# murdock_top_v4.net
KiCad netlist of a schematic drawn in EAGLE
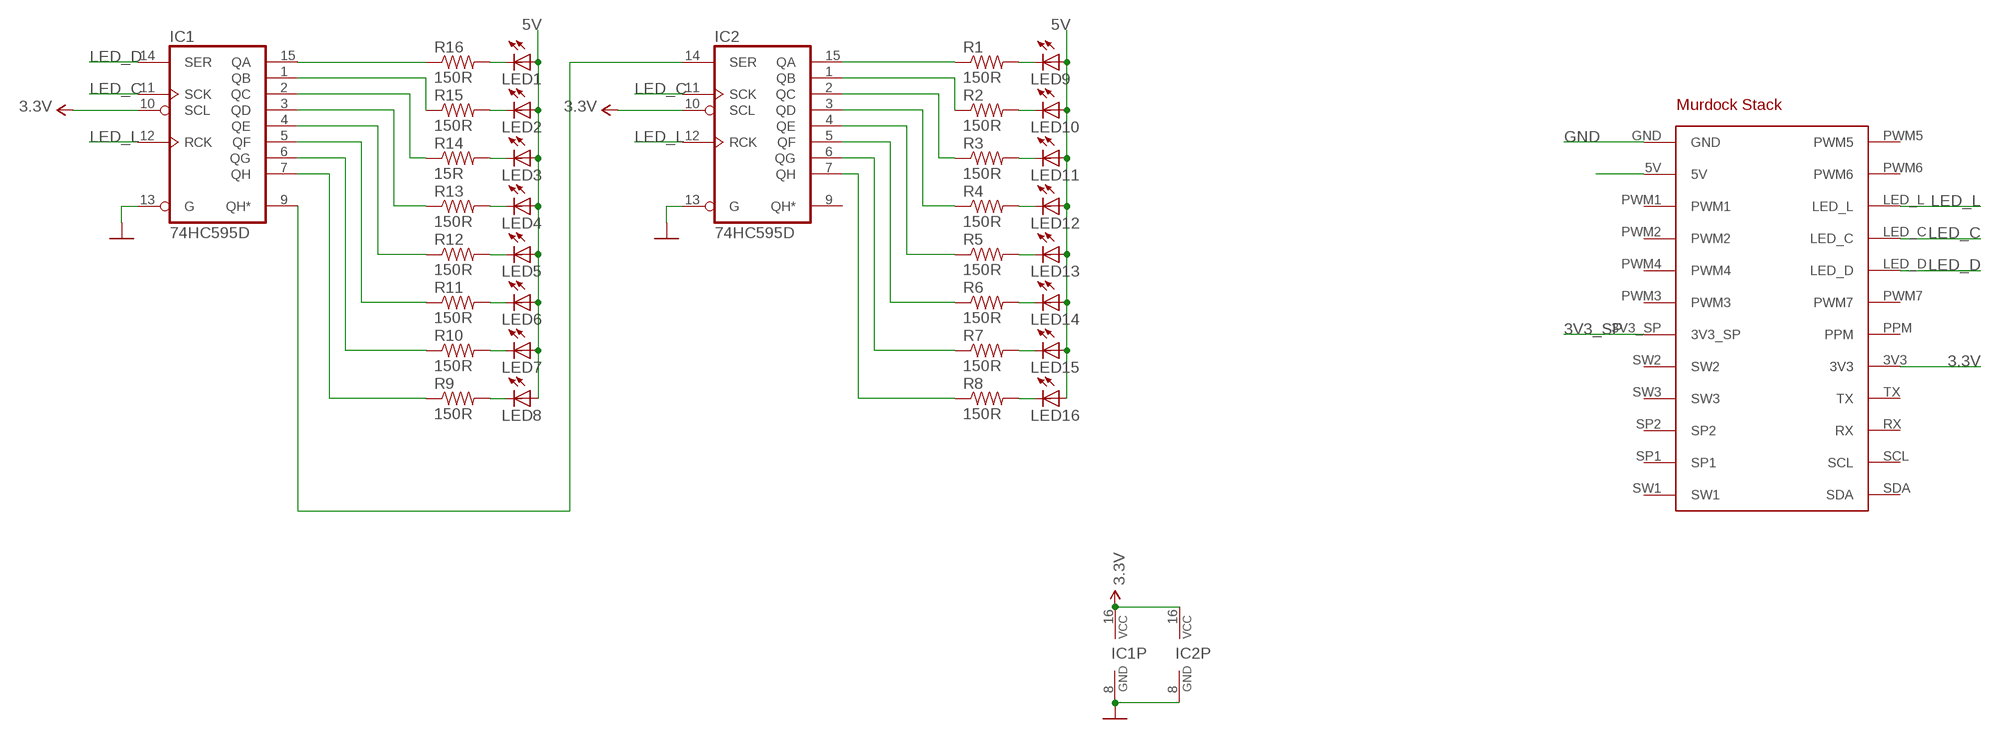
[diagram p0: schematic, sheet 1]

(export (version "E")
  (design (tool "Eeschema 10.0.6"))
  (components
    (comp (ref "IC1")
      (value "74HC595D")
      (footprint "eagle-import:SO16")
      (libsource (lib "eagle-import") (part "74595DHC"))
    )
    (comp (ref "IC2")
      (value "74HC595D")
      (footprint "eagle-import:SO16")
      (libsource (lib "eagle-import") (part "74595DHC"))
    )
    (comp (ref "LED1")
      (value "LGM47K")
      (footprint "eagle-import:LGM47K")
      (libsource (lib "eagle-import") (part "LGM47K"))
    )
    (comp (ref "LED2")
      (value "LGM47K")
      (footprint "eagle-import:LGM47K")
      (libsource (lib "eagle-import") (part "LGM47K"))
    )
    (comp (ref "LED3")
      (value "LGM47K")
      (footprint "eagle-import:LGM47K")
      (libsource (lib "eagle-import") (part "LGM47K"))
    )
    (comp (ref "LED4")
      (value "LGM47K")
      (footprint "eagle-import:LGM47K")
      (libsource (lib "eagle-import") (part "LGM47K"))
    )
    (comp (ref "LED5")
      (value "LGM47K")
      (footprint "eagle-import:LGM47K")
      (libsource (lib "eagle-import") (part "LGM47K"))
    )
    (comp (ref "LED6")
      (value "LGM47K")
      (footprint "eagle-import:LGM47K")
      (libsource (lib "eagle-import") (part "LGM47K"))
    )
    (comp (ref "LED7")
      (value "LGM47K")
      (footprint "eagle-import:LGM47K")
      (libsource (lib "eagle-import") (part "LGM47K"))
    )
    (comp (ref "LED8")
      (value "LGM47K")
      (footprint "eagle-import:LGM47K")
      (libsource (lib "eagle-import") (part "LGM47K"))
    )
    (comp (ref "LED9")
      (value "LGM47K")
      (footprint "eagle-import:LGM47K")
      (libsource (lib "eagle-import") (part "LGM47K"))
    )
    (comp (ref "LED10")
      (value "LGM47K")
      (footprint "eagle-import:LGM47K")
      (libsource (lib "eagle-import") (part "LGM47K"))
    )
    (comp (ref "LED11")
      (value "LGM47K")
      (footprint "eagle-import:LGM47K")
      (libsource (lib "eagle-import") (part "LGM47K"))
    )
    (comp (ref "LED12")
      (value "LGM47K")
      (footprint "eagle-import:LGM47K")
      (libsource (lib "eagle-import") (part "LGM47K"))
    )
    (comp (ref "LED13")
      (value "LGM47K")
      (footprint "eagle-import:LGM47K")
      (libsource (lib "eagle-import") (part "LGM47K"))
    )
    (comp (ref "LED14")
      (value "LGM47K")
      (footprint "eagle-import:LGM47K")
      (libsource (lib "eagle-import") (part "LGM47K"))
    )
    (comp (ref "LED15")
      (value "LGM47K")
      (footprint "eagle-import:LGM47K")
      (libsource (lib "eagle-import") (part "LGM47K"))
    )
    (comp (ref "LED16")
      (value "LGM47K")
      (footprint "eagle-import:LGM47K")
      (libsource (lib "eagle-import") (part "LGM47K"))
    )
    (comp (ref "R1")
      (value "150R")
      (footprint "eagle-import:0402-RES")
      (libsource (lib "eagle-import") (part "RESISTOR0402-RES"))
    )
    (comp (ref "R2")
      (value "150R")
      (footprint "eagle-import:0402-RES")
      (libsource (lib "eagle-import") (part "RESISTOR0402-RES"))
    )
    (comp (ref "R3")
      (value "150R")
      (footprint "eagle-import:0402-RES")
      (libsource (lib "eagle-import") (part "RESISTOR0402-RES"))
    )
    (comp (ref "R4")
      (value "150R")
      (footprint "eagle-import:0402-RES")
      (libsource (lib "eagle-import") (part "RESISTOR0402-RES"))
    )
    (comp (ref "R5")
      (value "150R")
      (footprint "eagle-import:0402-RES")
      (libsource (lib "eagle-import") (part "RESISTOR0402-RES"))
    )
    (comp (ref "R6")
      (value "150R")
      (footprint "eagle-import:0402-RES")
      (libsource (lib "eagle-import") (part "RESISTOR0402-RES"))
    )
    (comp (ref "R7")
      (value "150R")
      (footprint "eagle-import:0402-RES")
      (libsource (lib "eagle-import") (part "RESISTOR0402-RES"))
    )
    (comp (ref "R8")
      (value "150R")
      (footprint "eagle-import:0402-RES")
      (libsource (lib "eagle-import") (part "RESISTOR0402-RES"))
    )
    (comp (ref "R9")
      (value "150R")
      (footprint "eagle-import:0402-RES")
      (libsource (lib "eagle-import") (part "RESISTOR0402-RES"))
    )
    (comp (ref "R10")
      (value "150R")
      (footprint "eagle-import:0402-RES")
      (libsource (lib "eagle-import") (part "RESISTOR0402-RES"))
    )
    (comp (ref "R11")
      (value "150R")
      (footprint "eagle-import:0402-RES")
      (libsource (lib "eagle-import") (part "RESISTOR0402-RES"))
    )
    (comp (ref "R12")
      (value "150R")
      (footprint "eagle-import:0402-RES")
      (libsource (lib "eagle-import") (part "RESISTOR0402-RES"))
    )
    (comp (ref "R13")
      (value "150R")
      (footprint "eagle-import:0402-RES")
      (libsource (lib "eagle-import") (part "RESISTOR0402-RES"))
    )
    (comp (ref "R14")
      (value "15R")
      (footprint "eagle-import:0402-RES")
      (libsource (lib "eagle-import") (part "RESISTOR0402-RES"))
    )
    (comp (ref "R15")
      (value "150R")
      (footprint "eagle-import:0402-RES")
      (libsource (lib "eagle-import") (part "RESISTOR0402-RES"))
    )
    (comp (ref "R16")
      (value "150R")
      (footprint "eagle-import:0402-RES")
      (libsource (lib "eagle-import") (part "RESISTOR0402-RES"))
    )
    (comp (ref "X1")
      (value "MURDOCK_STACK")
      (footprint "eagle-import:MURDOCK_STACK")
      (libsource (lib "eagle-import") (part "MURDOCK_STACK"))
    )
  )
  (nets
    (net (code "1") (name "/3V3_SP") (class "Default")
      (node (ref "X1") (pin "3V3_SP") (pinfunction "3V3_SP_3V3_SP") (pintype "bidirectional"))
    )
    (net (code "2") (name "/5V") (class "Default")
      (node (ref "LED1") (pin "A") (pinfunction "A_A") (pintype "passive"))
      (node (ref "LED10") (pin "A") (pinfunction "A_A") (pintype "passive"))
      (node (ref "LED11") (pin "A") (pinfunction "A_A") (pintype "passive"))
      (node (ref "LED12") (pin "A") (pinfunction "A_A") (pintype "passive"))
      (node (ref "LED13") (pin "A") (pinfunction "A_A") (pintype "passive"))
      (node (ref "LED14") (pin "A") (pinfunction "A_A") (pintype "passive"))
      (node (ref "LED15") (pin "A") (pinfunction "A_A") (pintype "passive"))
      (node (ref "LED16") (pin "A") (pinfunction "A_A") (pintype "passive"))
      (node (ref "LED2") (pin "A") (pinfunction "A_A") (pintype "passive"))
      (node (ref "LED3") (pin "A") (pinfunction "A_A") (pintype "passive"))
      (node (ref "LED4") (pin "A") (pinfunction "A_A") (pintype "passive"))
      (node (ref "LED5") (pin "A") (pinfunction "A_A") (pintype "passive"))
      (node (ref "LED6") (pin "A") (pinfunction "A_A") (pintype "passive"))
      (node (ref "LED7") (pin "A") (pinfunction "A_A") (pintype "passive"))
      (node (ref "LED8") (pin "A") (pinfunction "A_A") (pintype "passive"))
      (node (ref "LED9") (pin "A") (pinfunction "A_A") (pintype "passive"))
      (node (ref "X1") (pin "5V") (pinfunction "5V_5V") (pintype "bidirectional"))
    )
    (net (code "3") (name "/LED_C") (class "Default")
      (node (ref "IC1") (pin "11") (pinfunction "SCK_11") (pintype "input"))
      (node (ref "IC2") (pin "11") (pinfunction "SCK_11") (pintype "input"))
      (node (ref "X1") (pin "LED_C") (pinfunction "LED_C_LED_C") (pintype "bidirectional"))
    )
    (net (code "4") (name "/LED_D") (class "Default")
      (node (ref "IC1") (pin "14") (pinfunction "SER_14") (pintype "input"))
      (node (ref "X1") (pin "LED_D") (pinfunction "LED_D_LED_D") (pintype "bidirectional"))
    )
    (net (code "5") (name "/LED_L") (class "Default")
      (node (ref "IC1") (pin "12") (pinfunction "RCK_12") (pintype "input"))
      (node (ref "IC2") (pin "12") (pinfunction "RCK_12") (pintype "input"))
      (node (ref "X1") (pin "LED_L") (pinfunction "LED_L_LED_L") (pintype "bidirectional"))
    )
    (net (code "6") (name "3.3V") (class "Default")
      (node (ref "IC1") (pin "10") (pinfunction "SCL_10") (pintype "input"))
      (node (ref "IC1") (pin "16") (pinfunction "VCC_16") (pintype "power_in"))
      (node (ref "IC2") (pin "10") (pinfunction "SCL_10") (pintype "input"))
      (node (ref "IC2") (pin "16") (pinfunction "VCC_16") (pintype "power_in"))
      (node (ref "X1") (pin "3V3") (pinfunction "3V3_3V3") (pintype "bidirectional"))
    )
    (net (code "7") (name "GND") (class "Default")
      (node (ref "IC1") (pin "13") (pinfunction "G_13") (pintype "input"))
      (node (ref "IC1") (pin "8") (pinfunction "GND_8") (pintype "power_in"))
      (node (ref "IC2") (pin "13") (pinfunction "G_13") (pintype "input"))
      (node (ref "IC2") (pin "8") (pinfunction "GND_8") (pintype "power_in"))
      (node (ref "X1") (pin "GND") (pinfunction "GND_GND") (pintype "bidirectional"))
    )
    (net (code "8") (name "Net-(IC1A-QA)") (class "Default")
      (node (ref "IC1") (pin "15") (pinfunction "QA_15") (pintype "tri_state"))
      (node (ref "R16") (pin "1") (pinfunction "1_1") (pintype "passive"))
    )
    (net (code "9") (name "Net-(IC1A-QB)") (class "Default")
      (node (ref "IC1") (pin "1") (pinfunction "QB_1") (pintype "tri_state"))
      (node (ref "R15") (pin "1") (pinfunction "1_1") (pintype "passive"))
    )
    (net (code "10") (name "Net-(IC1A-QC)") (class "Default")
      (node (ref "IC1") (pin "2") (pinfunction "QC_2") (pintype "tri_state"))
      (node (ref "R14") (pin "1") (pinfunction "1_1") (pintype "passive"))
    )
    (net (code "11") (name "Net-(IC1A-QD)") (class "Default")
      (node (ref "IC1") (pin "3") (pinfunction "QD_3") (pintype "tri_state"))
      (node (ref "R13") (pin "1") (pinfunction "1_1") (pintype "passive"))
    )
    (net (code "12") (name "Net-(IC1A-QE)") (class "Default")
      (node (ref "IC1") (pin "4") (pinfunction "QE_4") (pintype "tri_state"))
      (node (ref "R12") (pin "1") (pinfunction "1_1") (pintype "passive"))
    )
    (net (code "13") (name "Net-(IC1A-QF)") (class "Default")
      (node (ref "IC1") (pin "5") (pinfunction "QF_5") (pintype "tri_state"))
      (node (ref "R11") (pin "1") (pinfunction "1_1") (pintype "passive"))
    )
    (net (code "14") (name "Net-(IC1A-QG)") (class "Default")
      (node (ref "IC1") (pin "6") (pinfunction "QG_6") (pintype "tri_state"))
      (node (ref "R10") (pin "1") (pinfunction "1_1") (pintype "passive"))
    )
    (net (code "15") (name "Net-(IC1A-QH)") (class "Default")
      (node (ref "IC1") (pin "7") (pinfunction "QH_7") (pintype "tri_state"))
      (node (ref "R9") (pin "1") (pinfunction "1_1") (pintype "passive"))
    )
    (net (code "16") (name "Net-(IC1A-QH*)") (class "Default")
      (node (ref "IC1") (pin "9") (pinfunction "QH*_9") (pintype "tri_state"))
      (node (ref "IC2") (pin "14") (pinfunction "SER_14") (pintype "input"))
    )
    (net (code "17") (name "Net-(IC2A-QA)") (class "Default")
      (node (ref "IC2") (pin "15") (pinfunction "QA_15") (pintype "tri_state"))
      (node (ref "R1") (pin "1") (pinfunction "1_1") (pintype "passive"))
    )
    (net (code "18") (name "Net-(IC2A-QB)") (class "Default")
      (node (ref "IC2") (pin "1") (pinfunction "QB_1") (pintype "tri_state"))
      (node (ref "R2") (pin "1") (pinfunction "1_1") (pintype "passive"))
    )
    (net (code "19") (name "Net-(IC2A-QC)") (class "Default")
      (node (ref "IC2") (pin "2") (pinfunction "QC_2") (pintype "tri_state"))
      (node (ref "R3") (pin "1") (pinfunction "1_1") (pintype "passive"))
    )
    (net (code "20") (name "Net-(IC2A-QD)") (class "Default")
      (node (ref "IC2") (pin "3") (pinfunction "QD_3") (pintype "tri_state"))
      (node (ref "R4") (pin "1") (pinfunction "1_1") (pintype "passive"))
    )
    (net (code "21") (name "Net-(IC2A-QE)") (class "Default")
      (node (ref "IC2") (pin "4") (pinfunction "QE_4") (pintype "tri_state"))
      (node (ref "R5") (pin "1") (pinfunction "1_1") (pintype "passive"))
    )
    (net (code "22") (name "Net-(IC2A-QF)") (class "Default")
      (node (ref "IC2") (pin "5") (pinfunction "QF_5") (pintype "tri_state"))
      (node (ref "R6") (pin "1") (pinfunction "1_1") (pintype "passive"))
    )
    (net (code "23") (name "Net-(IC2A-QG)") (class "Default")
      (node (ref "IC2") (pin "6") (pinfunction "QG_6") (pintype "tri_state"))
      (node (ref "R7") (pin "1") (pinfunction "1_1") (pintype "passive"))
    )
    (net (code "24") (name "Net-(IC2A-QH)") (class "Default")
      (node (ref "IC2") (pin "7") (pinfunction "QH_7") (pintype "tri_state"))
      (node (ref "R8") (pin "1") (pinfunction "1_1") (pintype "passive"))
    )
    (net (code "25") (name "Net-(LED1-C)") (class "Default")
      (node (ref "LED1") (pin "K") (pinfunction "C_K") (pintype "passive"))
      (node (ref "R16") (pin "2") (pinfunction "2_2") (pintype "passive"))
    )
    (net (code "26") (name "Net-(LED2-C)") (class "Default")
      (node (ref "LED2") (pin "K") (pinfunction "C_K") (pintype "passive"))
      (node (ref "R15") (pin "2") (pinfunction "2_2") (pintype "passive"))
    )
    (net (code "27") (name "Net-(LED3-C)") (class "Default")
      (node (ref "LED3") (pin "K") (pinfunction "C_K") (pintype "passive"))
      (node (ref "R14") (pin "2") (pinfunction "2_2") (pintype "passive"))
    )
    (net (code "28") (name "Net-(LED4-C)") (class "Default")
      (node (ref "LED4") (pin "K") (pinfunction "C_K") (pintype "passive"))
      (node (ref "R13") (pin "2") (pinfunction "2_2") (pintype "passive"))
    )
    (net (code "29") (name "Net-(LED5-C)") (class "Default")
      (node (ref "LED5") (pin "K") (pinfunction "C_K") (pintype "passive"))
      (node (ref "R12") (pin "2") (pinfunction "2_2") (pintype "passive"))
    )
    (net (code "30") (name "Net-(LED6-C)") (class "Default")
      (node (ref "LED6") (pin "K") (pinfunction "C_K") (pintype "passive"))
      (node (ref "R11") (pin "2") (pinfunction "2_2") (pintype "passive"))
    )
    (net (code "31") (name "Net-(LED7-C)") (class "Default")
      (node (ref "LED7") (pin "K") (pinfunction "C_K") (pintype "passive"))
      (node (ref "R10") (pin "2") (pinfunction "2_2") (pintype "passive"))
    )
    (net (code "32") (name "Net-(LED8-C)") (class "Default")
      (node (ref "LED8") (pin "K") (pinfunction "C_K") (pintype "passive"))
      (node (ref "R9") (pin "2") (pinfunction "2_2") (pintype "passive"))
    )
    (net (code "33") (name "Net-(LED9-C)") (class "Default")
      (node (ref "LED9") (pin "K") (pinfunction "C_K") (pintype "passive"))
      (node (ref "R1") (pin "2") (pinfunction "2_2") (pintype "passive"))
    )
    (net (code "34") (name "Net-(LED10-C)") (class "Default")
      (node (ref "LED10") (pin "K") (pinfunction "C_K") (pintype "passive"))
      (node (ref "R2") (pin "2") (pinfunction "2_2") (pintype "passive"))
    )
    (net (code "35") (name "Net-(LED11-C)") (class "Default")
      (node (ref "LED11") (pin "K") (pinfunction "C_K") (pintype "passive"))
      (node (ref "R3") (pin "2") (pinfunction "2_2") (pintype "passive"))
    )
    (net (code "36") (name "Net-(LED12-C)") (class "Default")
      (node (ref "LED12") (pin "K") (pinfunction "C_K") (pintype "passive"))
      (node (ref "R4") (pin "2") (pinfunction "2_2") (pintype "passive"))
    )
    (net (code "37") (name "Net-(LED13-C)") (class "Default")
      (node (ref "LED13") (pin "K") (pinfunction "C_K") (pintype "passive"))
      (node (ref "R5") (pin "2") (pinfunction "2_2") (pintype "passive"))
    )
    (net (code "38") (name "Net-(LED14-C)") (class "Default")
      (node (ref "LED14") (pin "K") (pinfunction "C_K") (pintype "passive"))
      (node (ref "R6") (pin "2") (pinfunction "2_2") (pintype "passive"))
    )
    (net (code "39") (name "Net-(LED15-C)") (class "Default")
      (node (ref "LED15") (pin "K") (pinfunction "C_K") (pintype "passive"))
      (node (ref "R7") (pin "2") (pinfunction "2_2") (pintype "passive"))
    )
    (net (code "40") (name "Net-(LED16-C)") (class "Default")
      (node (ref "LED16") (pin "K") (pinfunction "C_K") (pintype "passive"))
      (node (ref "R8") (pin "2") (pinfunction "2_2") (pintype "passive"))
    )
    (net (code "41") (name "unconnected-(IC2A-QH*-Pad9)") (class "Default")
      (node (ref "IC2") (pin "9") (pinfunction "QH*_9") (pintype "tri_state"))
    )
    (net (code "42") (name "unconnected-(X1-PadPPM)") (class "Default")
      (node (ref "X1") (pin "PPM") (pinfunction "PPM_PPM") (pintype "bidirectional"))
    )
    (net (code "43") (name "unconnected-(X1-PadPWM1)") (class "Default")
      (node (ref "X1") (pin "PWM1") (pinfunction "PWM1_PWM1") (pintype "bidirectional"))
    )
    (net (code "44") (name "unconnected-(X1-PadPWM2)") (class "Default")
      (node (ref "X1") (pin "PWM2") (pinfunction "PWM2_PWM2") (pintype "bidirectional"))
    )
    (net (code "45") (name "unconnected-(X1-PadPWM3)") (class "Default")
      (node (ref "X1") (pin "PWM3") (pinfunction "PWM3_PWM3") (pintype "bidirectional"))
    )
    (net (code "46") (name "unconnected-(X1-PadPWM4)") (class "Default")
      (node (ref "X1") (pin "PWM4") (pinfunction "PWM4_PWM4") (pintype "bidirectional"))
    )
    (net (code "47") (name "unconnected-(X1-PadPWM5)") (class "Default")
      (node (ref "X1") (pin "PWM5") (pinfunction "PWM5_PWM5") (pintype "bidirectional"))
    )
    (net (code "48") (name "unconnected-(X1-PadPWM6)") (class "Default")
      (node (ref "X1") (pin "PWM6") (pinfunction "PWM6_PWM6") (pintype "bidirectional"))
    )
    (net (code "49") (name "unconnected-(X1-PadPWM7)") (class "Default")
      (node (ref "X1") (pin "PWM7") (pinfunction "PWM7_PWM7") (pintype "bidirectional"))
    )
    (net (code "50") (name "unconnected-(X1-PadRX)") (class "Default")
      (node (ref "X1") (pin "RX") (pinfunction "RX_RX") (pintype "bidirectional"))
    )
    (net (code "51") (name "unconnected-(X1-PadSCL)") (class "Default")
      (node (ref "X1") (pin "SCL") (pinfunction "SCL_SCL") (pintype "bidirectional"))
    )
    (net (code "52") (name "unconnected-(X1-PadSDA)") (class "Default")
      (node (ref "X1") (pin "SDA") (pinfunction "SDA_SDA") (pintype "bidirectional"))
    )
    (net (code "53") (name "unconnected-(X1-PadSP1)") (class "Default")
      (node (ref "X1") (pin "SP1") (pinfunction "SP1_SP1") (pintype "bidirectional"))
    )
    (net (code "54") (name "unconnected-(X1-PadSP2)") (class "Default")
      (node (ref "X1") (pin "SP2") (pinfunction "SP2_SP2") (pintype "bidirectional"))
    )
    (net (code "55") (name "unconnected-(X1-PadSW1)") (class "Default")
      (node (ref "X1") (pin "SW1") (pinfunction "SW1_SW1") (pintype "bidirectional"))
    )
    (net (code "56") (name "unconnected-(X1-PadSW2)") (class "Default")
      (node (ref "X1") (pin "SW2") (pinfunction "SW2_SW2") (pintype "bidirectional"))
    )
    (net (code "57") (name "unconnected-(X1-PadSW3)") (class "Default")
      (node (ref "X1") (pin "SW3") (pinfunction "SW3_SW3") (pintype "bidirectional"))
    )
    (net (code "58") (name "unconnected-(X1-PadTX)") (class "Default")
      (node (ref "X1") (pin "TX") (pinfunction "TX_TX") (pintype "bidirectional"))
    )
  )
)
